# Sheet1.net
KiCad netlist of a schematic drawn in Altium Designer
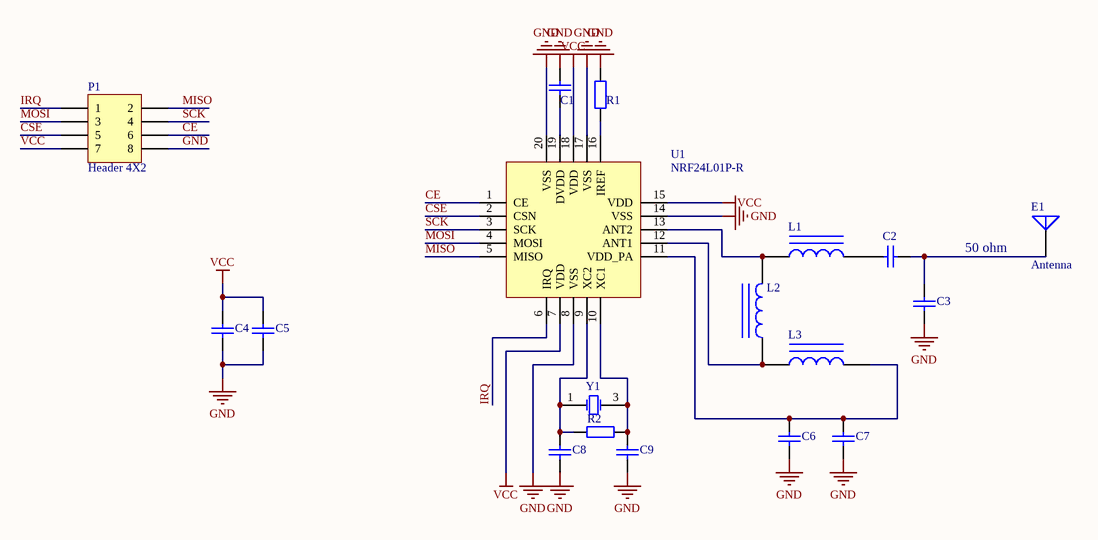
[diagram p0: Sheet1.SchDoc]

(export (version "E")
  (design (tool "Eeschema 10.0.6"))
  (components
    (comp (ref "C1")
      (value "33nF (333) 20% 50V")
      (footprint "0402_C")
      (description "贴片电容")
      (libsource (lib "Miscellaneous Devices LC") (part "0402 33nF (333) 20% 50V"))
    )
    (comp (ref "C2")
      (value "1.5pF (1R5) 0.25pF 50V")
      (footprint "0402_C")
      (description "贴片电容")
      (libsource (lib "Miscellaneous Devices LC") (part "0402 1.5pF (1R5) 0.25pF 50V"))
    )
    (comp (ref "C3")
      (value "1pF (1R0) 0.25pF 50V")
      (footprint "0402_C")
      (description "贴片电容")
      (libsource (lib "Miscellaneous Devices LC") (part "0402 1pF (1R0) 0.25pF 50V"))
    )
    (comp (ref "C4")
      (value "1nF (102) 10% 50V")
      (footprint "0402_C")
      (description "贴片电容")
      (libsource (lib "Miscellaneous Devices LC") (part "0402 1nF (102) 10% 50V"))
    )
    (comp (ref "C5")
      (value "10nF (103) 10% 50V")
      (footprint "0402_C")
      (description "贴片电容")
      (libsource (lib "Miscellaneous Devices LC") (part "0402 10nF (103) 10% 50V"))
    )
    (comp (ref "C6")
      (value "2.2nF (222) 10% 50V")
      (footprint "0402_C")
      (description "贴片电容")
      (libsource (lib "Miscellaneous Devices LC") (part "0402 2.2nF (222) 10% 50V"))
    )
    (comp (ref "C7")
      (value "4.7pF (4R7) 0.25pF 50V")
      (footprint "0402_C")
      (description "贴片电容")
      (libsource (lib "Miscellaneous Devices LC") (part "0402 4.7pF (4R7) 0.25pF 50V"))
    )
    (comp (ref "C8")
      (value "10pF (100) 5% 50V")
      (footprint "0402_C")
      (description "贴片电容")
      (libsource (lib "Miscellaneous Devices LC") (part "0402 10pF (100) 5% 50V"))
    )
    (comp (ref "C9")
      (value "10pF (100) 5% 50V")
      (footprint "0402_C")
      (description "贴片电容")
      (libsource (lib "Miscellaneous Devices LC") (part "0402 10pF (100) 5% 50V"))
    )
    (comp (ref "E1")
      (value "Antenna")
      (footprint "MIFA天线")
      (description "Generic Antenna")
      (fields (field (name "PUBLISHER") "Altium Limited"))
      (libsource (lib "Miscellaneous Devices") (part "Antenna"))
    )
    (comp (ref "L1")
      (value "3.9nH 3%")
      (footprint "0402_L")
      (description "贴片电感")
      (libsource (lib "Miscellaneous Devices LC") (part "0402 3.9nH 3%"))
    )
    (comp (ref "L2")
      (value "8.2nH 5%")
      (footprint "0402_L")
      (description "贴片电感")
      (libsource (lib "Miscellaneous Devices LC") (part "0402 8.2nH 5%"))
    )
    (comp (ref "L3")
      (value "2.7nH 0.3nH")
      (footprint "0402_L")
      (description "贴片电感")
      (libsource (lib "Miscellaneous Devices LC") (part "0402 2.7nH 0.3nH"))
    )
    (comp (ref "P1")
      (value "Header 4X2")
      (footprint "HDR2X4")
      (description "Header, 4-Pin, Dual row")
      (fields (field (name "PUBLISHER") "Altium Limited"))
      (libsource (lib "Miscellaneous Connectors") (part "Header 4X2"))
    )
    (comp (ref "R1")
      (value "22KΩ (2202) ±1%")
      (footprint "0402_R")
      (description "贴片电阻")
      (libsource (lib "Miscellaneous Devices LC") (part "0402 22KΩ (2202) 1%"))
    )
    (comp (ref "R2")
      (value "1MΩ (1004) ±1%")
      (footprint "0402_R")
      (description "贴片电阻")
      (libsource (lib "Miscellaneous Devices LC") (part "0402 1MΩ (1004) 1%"))
    )
    (comp (ref "U1")
      (value "NRF24L01P-R")
      (footprint "QFN-20_4x4x05P")
      (description "无线")
      (libsource (lib "Miscellaneous Devices LC") (part "NRF24L01P-R_[C8791]"))
    )
    (comp (ref "Y1")
      (value "16MHZ 9PF 10PPM")
      (footprint "SMD-3225_4P")
      (description "贴片晶振")
      (libsource (lib "Miscellaneous Devices LC") (part "SMD-3225_4P  16MHZ 9PF 10PPM"))
    )
  )
  (nets
    (net (code "1") (name "/CE") (class "Default")
      (node (ref "P1") (pin "6") (pinfunction "6_6") (pintype "passive"))
      (node (ref "U1") (pin "1") (pinfunction "CE_1") (pintype "passive"))
    )
    (net (code "2") (name "/CSE") (class "Default")
      (node (ref "P1") (pin "5") (pinfunction "5_5") (pintype "passive"))
      (node (ref "U1") (pin "2") (pinfunction "CSN_2") (pintype "passive"))
    )
    (net (code "3") (name "/IRQ") (class "Default")
      (node (ref "P1") (pin "1") (pinfunction "1_1") (pintype "passive"))
      (node (ref "U1") (pin "6") (pinfunction "IRQ_6") (pintype "passive"))
    )
    (net (code "4") (name "/MISO") (class "Default")
      (node (ref "P1") (pin "2") (pinfunction "2_2") (pintype "passive"))
      (node (ref "U1") (pin "5") (pinfunction "MISO_5") (pintype "passive"))
    )
    (net (code "5") (name "/MOSI") (class "Default")
      (node (ref "P1") (pin "3") (pinfunction "3_3") (pintype "passive"))
      (node (ref "U1") (pin "4") (pinfunction "MOSI_4") (pintype "passive"))
    )
    (net (code "6") (name "/SCK") (class "Default")
      (node (ref "P1") (pin "4") (pinfunction "4_4") (pintype "passive"))
      (node (ref "U1") (pin "3") (pinfunction "SCK_3") (pintype "passive"))
    )
    (net (code "7") (name "GND") (class "Default")
      (node (ref "C1") (pin "2") (pinfunction "2_2") (pintype "passive"))
      (node (ref "C3") (pin "1") (pinfunction "1_1") (pintype "passive"))
      (node (ref "C4") (pin "1") (pinfunction "1_1") (pintype "passive"))
      (node (ref "C5") (pin "1") (pinfunction "1_1") (pintype "passive"))
      (node (ref "C6") (pin "1") (pinfunction "1_1") (pintype "passive"))
      (node (ref "C7") (pin "1") (pinfunction "1_1") (pintype "passive"))
      (node (ref "C8") (pin "1") (pinfunction "1_1") (pintype "passive"))
      (node (ref "C9") (pin "1") (pinfunction "1_1") (pintype "passive"))
      (node (ref "P1") (pin "8") (pinfunction "8_8") (pintype "passive"))
      (node (ref "R1") (pin "2") (pinfunction "2_2") (pintype "passive"))
      (node (ref "U1") (pin "14") (pinfunction "VSS_14") (pintype "passive"))
      (node (ref "U1") (pin "17") (pinfunction "VSS_17") (pintype "passive"))
      (node (ref "U1") (pin "20") (pinfunction "VSS_20") (pintype "passive"))
      (node (ref "U1") (pin "8") (pinfunction "VSS_8") (pintype "passive"))
    )
    (net (code "8") (name "Net-(C2-Pad1)") (class "Default")
      (node (ref "C2") (pin "1") (pinfunction "1_1") (pintype "passive"))
      (node (ref "L1") (pin "2") (pinfunction "2_2") (pintype "passive"))
    )
    (net (code "9") (name "Net-(E1-A)") (class "Default")
      (node (ref "C2") (pin "2") (pinfunction "2_2") (pintype "passive"))
      (node (ref "C3") (pin "2") (pinfunction "2_2") (pintype "passive"))
      (node (ref "E1") (pin "1") (pinfunction "A_1") (pintype "passive"))
    )
    (net (code "10") (name "Net-(U1-ANT1)") (class "Default")
      (node (ref "L2") (pin "1") (pinfunction "1_1") (pintype "passive"))
      (node (ref "L3") (pin "1") (pinfunction "1_1") (pintype "passive"))
      (node (ref "U1") (pin "12") (pinfunction "ANT1_12") (pintype "passive"))
    )
    (net (code "11") (name "Net-(U1-ANT2)") (class "Default")
      (node (ref "L1") (pin "1") (pinfunction "1_1") (pintype "passive"))
      (node (ref "L2") (pin "2") (pinfunction "2_2") (pintype "passive"))
      (node (ref "U1") (pin "13") (pinfunction "ANT2_13") (pintype "passive"))
    )
    (net (code "12") (name "Net-(U1-DVDD)") (class "Default")
      (node (ref "C1") (pin "1") (pinfunction "1_1") (pintype "passive"))
      (node (ref "U1") (pin "19") (pinfunction "DVDD_19") (pintype "passive"))
    )
    (net (code "13") (name "Net-(U1-IREF)") (class "Default")
      (node (ref "R1") (pin "1") (pinfunction "1_1") (pintype "passive"))
      (node (ref "U1") (pin "16") (pinfunction "IREF_16") (pintype "passive"))
    )
    (net (code "14") (name "Net-(U1-VDD_PA)") (class "Default")
      (node (ref "C6") (pin "2") (pinfunction "2_2") (pintype "passive"))
      (node (ref "C7") (pin "2") (pinfunction "2_2") (pintype "passive"))
      (node (ref "L3") (pin "2") (pinfunction "2_2") (pintype "passive"))
      (node (ref "U1") (pin "11") (pinfunction "VDD_PA_11") (pintype "passive"))
    )
    (net (code "15") (name "Net-(U1-XC1)") (class "Default")
      (node (ref "C9") (pin "2") (pinfunction "2_2") (pintype "passive"))
      (node (ref "R2") (pin "2") (pinfunction "2_2") (pintype "passive"))
      (node (ref "U1") (pin "10") (pinfunction "XC1_10") (pintype "passive"))
      (node (ref "Y1") (pin "3") (pinfunction "OSC2_3") (pintype "passive"))
    )
    (net (code "16") (name "Net-(U1-XC2)") (class "Default")
      (node (ref "C8") (pin "2") (pinfunction "2_2") (pintype "passive"))
      (node (ref "R2") (pin "1") (pinfunction "1_1") (pintype "passive"))
      (node (ref "U1") (pin "9") (pinfunction "XC2_9") (pintype "passive"))
      (node (ref "Y1") (pin "1") (pinfunction "OSC1_1") (pintype "passive"))
    )
    (net (code "17") (name "VCC") (class "Default")
      (node (ref "C4") (pin "2") (pinfunction "2_2") (pintype "passive"))
      (node (ref "C5") (pin "2") (pinfunction "2_2") (pintype "passive"))
      (node (ref "P1") (pin "7") (pinfunction "7_7") (pintype "passive"))
      (node (ref "U1") (pin "15") (pinfunction "VDD_15") (pintype "passive"))
      (node (ref "U1") (pin "18") (pinfunction "VDD_18") (pintype "passive"))
      (node (ref "U1") (pin "7") (pinfunction "VDD_7") (pintype "passive"))
    )
  )
)
